# datalogger_v1.net
KiCad netlist of a schematic drawn in EAGLE
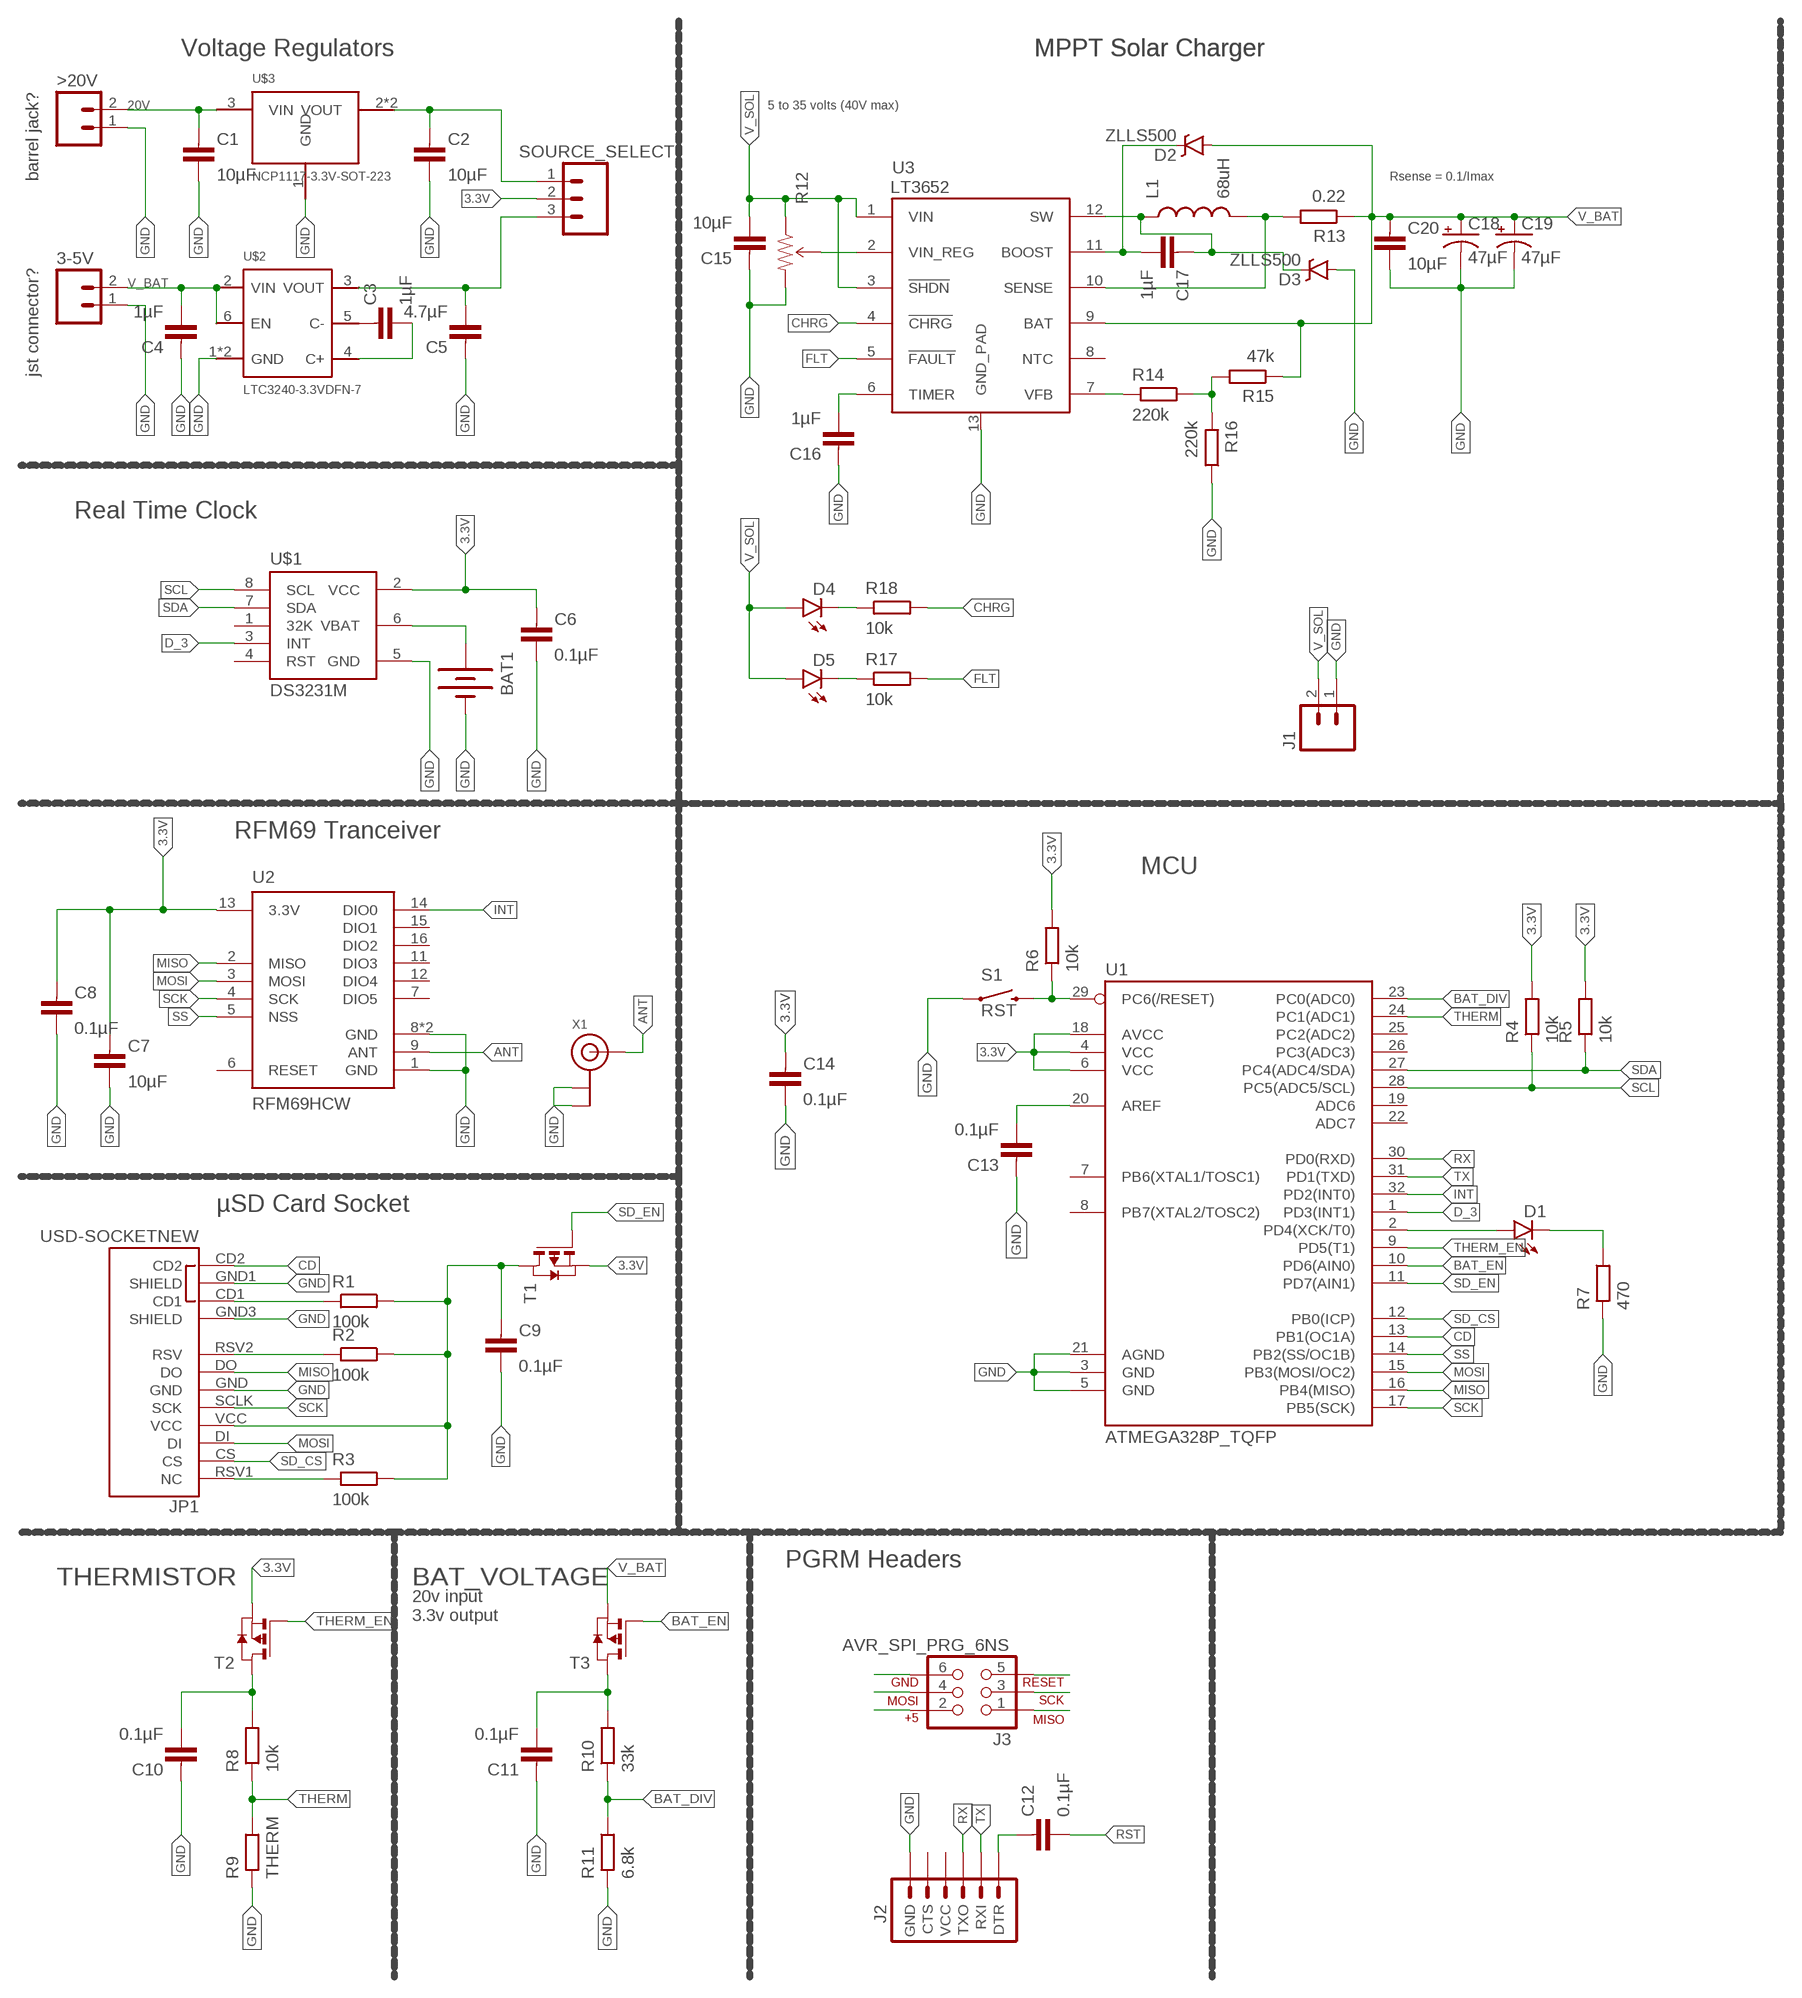
[diagram p0: schematic, sheet 1]

(export (version "E")
  (design (tool "Eeschema 10.0.6"))
  (components
    (comp (ref "3-5V")
      (value "M02LOCK")
      (footprint "eagle-import:1X02_LOCK")
      (libsource (lib "eagle-import") (part "M02LOCK"))
    )
    (comp (ref ">20V")
      (value "M02LOCK")
      (footprint "eagle-import:1X02_LOCK")
      (libsource (lib "eagle-import") (part "M02LOCK"))
    )
    (comp (ref "BAT1")
      (value "BATTERY12MM")
      (footprint "eagle-import:BATTCON_12MM")
      (libsource (lib "eagle-import") (part "BATTERY12MM"))
    )
    (comp (ref "C1")
      (value "10µF")
      (footprint "eagle-import:C0805-N")
      (libsource (lib "eagle-import") (part "CAPACITOR0805-N"))
    )
    (comp (ref "C2")
      (value "10µF")
      (footprint "eagle-import:C0805-N")
      (libsource (lib "eagle-import") (part "CAPACITOR0805-N"))
    )
    (comp (ref "C3")
      (value "1µF")
      (footprint "eagle-import:C0603-N")
      (libsource (lib "eagle-import") (part "CAPACITOR0603-N"))
    )
    (comp (ref "C4")
      (value "1µF")
      (footprint "eagle-import:C0603-N")
      (libsource (lib "eagle-import") (part "CAPACITOR0603-N"))
    )
    (comp (ref "C5")
      (value "4.7µF")
      (footprint "eagle-import:C0603-N")
      (libsource (lib "eagle-import") (part "CAPACITOR0603-N"))
    )
    (comp (ref "C6")
      (value "0.1µF")
      (footprint "eagle-import:C0603-N")
      (libsource (lib "eagle-import") (part "CAPACITOR0603-N"))
    )
    (comp (ref "C7")
      (value "10µF")
      (footprint "eagle-import:C0805-N")
      (libsource (lib "eagle-import") (part "CAPACITOR0805-N"))
    )
    (comp (ref "C8")
      (value "0.1µF")
      (footprint "eagle-import:C0603-N")
      (libsource (lib "eagle-import") (part "CAPACITOR0603-N"))
    )
    (comp (ref "C9")
      (value "0.1µF")
      (footprint "eagle-import:C0603-N")
      (libsource (lib "eagle-import") (part "CAPACITOR0603-N"))
    )
    (comp (ref "C10")
      (value "0.1µF")
      (footprint "eagle-import:C0603-N")
      (libsource (lib "eagle-import") (part "CAPACITOR0603-N"))
    )
    (comp (ref "C11")
      (value "0.1µF")
      (footprint "eagle-import:C0603-N")
      (libsource (lib "eagle-import") (part "CAPACITOR0603-N"))
    )
    (comp (ref "C12")
      (value "0.1µF")
      (footprint "eagle-import:C0603-N")
      (libsource (lib "eagle-import") (part "CAPACITOR0603-N"))
    )
    (comp (ref "C13")
      (value "0.1µF")
      (footprint "eagle-import:C0603-N")
      (libsource (lib "eagle-import") (part "CAPACITOR0603-N"))
    )
    (comp (ref "C14")
      (value "0.1µF")
      (footprint "eagle-import:C0603-N")
      (libsource (lib "eagle-import") (part "CAPACITOR0603-N"))
    )
    (comp (ref "C15")
      (value "10µF")
      (footprint "eagle-import:C0805-N")
      (libsource (lib "eagle-import") (part "CAPACITOR0805-N"))
    )
    (comp (ref "C16")
      (value "1µF")
      (footprint "eagle-import:C0603-N")
      (libsource (lib "eagle-import") (part "CAPACITOR0603-N"))
    )
    (comp (ref "C17")
      (value "1µF")
      (footprint "eagle-import:C0603-N")
      (libsource (lib "eagle-import") (part "CAPACITOR0603-N"))
    )
    (comp (ref "C18")
      (value "47µF")
      (footprint "eagle-import:EN_J2")
      (libsource (lib "eagle-import") (part "CAP_POLEN_J2"))
    )
    (comp (ref "C19")
      (value "47µF")
      (footprint "eagle-import:EN_J2")
      (libsource (lib "eagle-import") (part "CAP_POLEN_J2"))
    )
    (comp (ref "C20")
      (value "10µF")
      (footprint "eagle-import:C0805-N")
      (libsource (lib "eagle-import") (part "CAPACITOR0805-N"))
    )
    (comp (ref "D1")
      (value "LED0603")
      (footprint "eagle-import:LED-0603")
      (libsource (lib "eagle-import") (part "LED0603"))
    )
    (comp (ref "D2")
      (value "ZLLS500")
      (footprint "eagle-import:SOT23-3")
      (libsource (lib "eagle-import") (part "ZLLS500ZLLS500"))
    )
    (comp (ref "D3")
      (value "ZLLS500")
      (footprint "eagle-import:SOT23-3")
      (libsource (lib "eagle-import") (part "ZLLS500ZLLS500"))
    )
    (comp (ref "D4")
      (value "LED0603")
      (footprint "eagle-import:LED-0603")
      (libsource (lib "eagle-import") (part "LED0603"))
    )
    (comp (ref "D5")
      (value "LED0603")
      (footprint "eagle-import:LED-0603")
      (libsource (lib "eagle-import") (part "LED0603"))
    )
    (comp (ref "J1")
      (value "M02LOCK")
      (footprint "eagle-import:1X02_LOCK")
      (libsource (lib "eagle-import") (part "M02LOCK"))
    )
    (comp (ref "J2")
      (value "ARDUINO_SERIAL_PROGRAMLOCK")
      (footprint "eagle-import:1X06_LOCK")
      (libsource (lib "eagle-import") (part "ARDUINO_SERIAL_PROGRAMLOCK"))
    )
    (comp (ref "J3")
      (value "AVR_SPI_PRG_6NS")
      (footprint "eagle-import:2X3-NS")
      (libsource (lib "eagle-import") (part "AVR_SPI_PRG_6NS"))
    )
    (comp (ref "JP1")
      (value "USD-SOCKETNEW")
      (footprint "eagle-import:MICRO-SD-SOCKET-PP")
      (libsource (lib "eagle-import") (part "USD-SOCKETNEW"))
    )
    (comp (ref "L1")
      (value "68uH")
      (footprint "eagle-import:CR75")
      (libsource (lib "eagle-import") (part "INDUCTOR68UH-1A"))
    )
    (comp (ref "R1")
      (value "100k")
      (footprint "eagle-import:R0603-N")
      (libsource (lib "eagle-import") (part "RESISTOR0603-N"))
    )
    (comp (ref "R2")
      (value "100k")
      (footprint "eagle-import:R0603-N")
      (libsource (lib "eagle-import") (part "RESISTOR0603-N"))
    )
    (comp (ref "R3")
      (value "100k")
      (footprint "eagle-import:R0603-N")
      (libsource (lib "eagle-import") (part "RESISTOR0603-N"))
    )
    (comp (ref "R4")
      (value "10k")
      (footprint "eagle-import:R0603-N")
      (libsource (lib "eagle-import") (part "RESISTOR0603-N"))
    )
    (comp (ref "R5")
      (value "10k")
      (footprint "eagle-import:R0603-N")
      (libsource (lib "eagle-import") (part "RESISTOR0603-N"))
    )
    (comp (ref "R6")
      (value "10k")
      (footprint "eagle-import:R0603-N")
      (libsource (lib "eagle-import") (part "RESISTOR0603-N"))
    )
    (comp (ref "R7")
      (value "470")
      (footprint "eagle-import:R0603-N")
      (libsource (lib "eagle-import") (part "RESISTOR0603-N"))
    )
    (comp (ref "R8")
      (value "10k")
      (footprint "eagle-import:R0603-N")
      (libsource (lib "eagle-import") (part "RESISTOR0603-N"))
    )
    (comp (ref "R9")
      (value "THERM")
      (footprint "eagle-import:R0603-N")
      (libsource (lib "eagle-import") (part "RESISTOR0603-N"))
    )
    (comp (ref "R10")
      (value "33k")
      (footprint "eagle-import:R0603-N")
      (libsource (lib "eagle-import") (part "RESISTOR0603-N"))
    )
    (comp (ref "R11")
      (value "6.8k")
      (footprint "eagle-import:R0603-N")
      (libsource (lib "eagle-import") (part "RESISTOR0603-N"))
    )
    (comp (ref "R12")
      (value "TRIMPOT")
      (footprint "eagle-import:TRIMPOT-5MM-V2")
      (libsource (lib "eagle-import") (part "TRIMPOT"))
    )
    (comp (ref "R13")
      (value "0.22")
      (footprint "eagle-import:R0603-N")
      (libsource (lib "eagle-import") (part "RESISTOR0603-N"))
    )
    (comp (ref "R14")
      (value "220k")
      (footprint "eagle-import:R0603-N")
      (libsource (lib "eagle-import") (part "RESISTOR0603-N"))
    )
    (comp (ref "R15")
      (value "47k")
      (footprint "eagle-import:R0603-N")
      (libsource (lib "eagle-import") (part "RESISTOR0603-N"))
    )
    (comp (ref "R16")
      (value "220k")
      (footprint "eagle-import:R0603-N")
      (libsource (lib "eagle-import") (part "RESISTOR0603-N"))
    )
    (comp (ref "R17")
      (value "10k")
      (footprint "eagle-import:R0603-N")
      (libsource (lib "eagle-import") (part "RESISTOR0603-N"))
    )
    (comp (ref "R18")
      (value "10k")
      (footprint "eagle-import:R0603-N")
      (libsource (lib "eagle-import") (part "RESISTOR0603-N"))
    )
    (comp (ref "S1")
      (value "RST")
      (footprint "eagle-import:TACTILE_SWITCH_SMD_4.6X2.8MM")
      (libsource (lib "eagle-import") (part "SWITCH-MOMENTARY-2SMD-4.6X2.8MM"))
    )
    (comp (ref "SOURCE_SELECT")
      (value "M03LOCK")
      (footprint "eagle-import:1X03_LOCK")
      (libsource (lib "eagle-import") (part "M03LOCK"))
    )
    (comp (ref "T1")
      (value "PMOSSOT23")
      (footprint "eagle-import:SOT-23")
      (libsource (lib "eagle-import") (part "PMOSSOT23"))
    )
    (comp (ref "T2")
      (value "PMOSSOT23")
      (footprint "eagle-import:SOT-23")
      (libsource (lib "eagle-import") (part "PMOSSOT23"))
    )
    (comp (ref "T3")
      (value "PMOSSOT23")
      (footprint "eagle-import:SOT-23")
      (libsource (lib "eagle-import") (part "PMOSSOT23"))
    )
    (comp (ref "U$1")
      (value "DS3231M")
      (footprint "eagle-import:SO08")
      (libsource (lib "eagle-import") (part "DS3231M"))
    )
    (comp (ref "U$2")
      (value "LTC3240-3.3VDFN-7")
      (footprint "eagle-import:DFN200X200X80-7N")
      (libsource (lib "eagle-import") (part "LTC3240-3.3VDFN-7"))
    )
    (comp (ref "U$3")
      (value "NCP1117-3.3V-SOT-223")
      (footprint "eagle-import:SOT223")
      (libsource (lib "eagle-import") (part "NCP1117-3.3V-SOT-223"))
    )
    (comp (ref "U1")
      (value "ATMEGA328P_TQFP")
      (footprint "eagle-import:TQFP32-08")
      (libsource (lib "eagle-import") (part "ATMEGA328P_TQFP"))
    )
    (comp (ref "U2")
      (value "RFM69HCW")
      (footprint "eagle-import:RFM69HCW-XXXS2")
      (libsource (lib "eagle-import") (part "RFM69HCW"))
    )
    (comp (ref "U3")
      (value "LT3652")
      (footprint "eagle-import:MSOP-12_GND")
      (libsource (lib "eagle-import") (part "LT3652"))
    )
    (comp (ref "X1")
      (value "ADAFRUIT_ANTENNA_U.FL")
      (footprint "eagle-import:ADAFRUIT_U.FL")
      (libsource (lib "eagle-import") (part "ADAFRUIT_ANTENNA_U.FL"))
    )
  )
  (nets
    (net (code "1") (name "/20V") (class "Default")
      (node (ref ">20V") (pin "2") (pinfunction "2_2") (pintype "passive"))
      (node (ref "C1") (pin "1") (pinfunction "1_1") (pintype "passive"))
      (node (ref "U$3") (pin "3") (pinfunction "VIN_3") (pintype "bidirectional"))
    )
    (net (code "2") (name "3.3V") (class "Default")
      (node (ref "C14") (pin "1") (pinfunction "1_1") (pintype "passive"))
      (node (ref "C6") (pin "1") (pinfunction "1_1") (pintype "passive"))
      (node (ref "C7") (pin "1") (pinfunction "1_1") (pintype "passive"))
      (node (ref "C8") (pin "1") (pinfunction "1_1") (pintype "passive"))
      (node (ref "J3") (pin "2") (pinfunction "2_2") (pintype "passive"))
      (node (ref "R4") (pin "2") (pinfunction "P$2_2") (pintype "passive"))
      (node (ref "R5") (pin "2") (pinfunction "P$2_2") (pintype "passive"))
      (node (ref "R6") (pin "2") (pinfunction "P$2_2") (pintype "passive"))
      (node (ref "SOURCE_SELECT") (pin "2") (pinfunction "2_2") (pintype "passive"))
      (node (ref "T1") (pin "2") (pinfunction "S_2") (pintype "passive"))
      (node (ref "T2") (pin "2") (pinfunction "S_2") (pintype "passive"))
      (node (ref "U$1") (pin "2") (pinfunction "VCC_2") (pintype "power_in"))
      (node (ref "U1") (pin "18") (pinfunction "AVCC_18") (pintype "bidirectional"))
      (node (ref "U1") (pin "4") (pinfunction "VCC_4") (pintype "bidirectional"))
      (node (ref "U1") (pin "6") (pinfunction "VCC_6") (pintype "bidirectional"))
      (node (ref "U2") (pin "13") (pinfunction "3.3V_13") (pintype "power_in"))
    )
    (net (code "3") (name "ANT") (class "Default")
      (node (ref "U2") (pin "9") (pinfunction "ANT_9") (pintype "passive"))
      (node (ref "X1") (pin "3") (pinfunction "SIGNAL_3") (pintype "passive"))
    )
    (net (code "4") (name "BAT_DIV") (class "Default")
      (node (ref "R10") (pin "1") (pinfunction "P$1_1") (pintype "passive"))
      (node (ref "R11") (pin "2") (pinfunction "P$2_2") (pintype "passive"))
      (node (ref "U1") (pin "23") (pinfunction "PC0(ADC0)_23") (pintype "bidirectional"))
    )
    (net (code "5") (name "BAT_EN") (class "Default")
      (node (ref "T3") (pin "3") (pinfunction "G_3") (pintype "passive"))
      (node (ref "U1") (pin "10") (pinfunction "PD6(AIN0)_10") (pintype "bidirectional"))
    )
    (net (code "6") (name "CD") (class "Default")
      (node (ref "JP1") (pin "CD2") (pinfunction "CD2_CD2") (pintype "bidirectional"))
      (node (ref "U1") (pin "13") (pinfunction "PB1(OC1A)_13") (pintype "bidirectional"))
    )
    (net (code "7") (name "CHRG") (class "Default")
      (node (ref "R18") (pin "2") (pinfunction "P$2_2") (pintype "passive"))
      (node (ref "U3") (pin "4") (pinfunction "~{CHRG}_4") (pintype "bidirectional"))
    )
    (net (code "8") (name "D_3") (class "Default")
      (node (ref "U$1") (pin "3") (pinfunction "INT_3") (pintype "bidirectional"))
      (node (ref "U1") (pin "1") (pinfunction "PD3(INT1)_1") (pintype "bidirectional"))
    )
    (net (code "9") (name "FLT") (class "Default")
      (node (ref "R17") (pin "2") (pinfunction "P$2_2") (pintype "passive"))
      (node (ref "U3") (pin "5") (pinfunction "~{FAULT}_5") (pintype "bidirectional"))
    )
    (net (code "10") (name "GND") (class "Default")
      (node (ref "3-5V") (pin "1") (pinfunction "1_1") (pintype "passive"))
      (node (ref ">20V") (pin "1") (pinfunction "1_1") (pintype "passive"))
      (node (ref "BAT1") (pin "GND") (pinfunction "-_GND") (pintype "power_in"))
      (node (ref "C1") (pin "2") (pinfunction "2_2") (pintype "passive"))
      (node (ref "C10") (pin "1") (pinfunction "1_1") (pintype "passive"))
      (node (ref "C11") (pin "1") (pinfunction "1_1") (pintype "passive"))
      (node (ref "C13") (pin "1") (pinfunction "1_1") (pintype "passive"))
      (node (ref "C14") (pin "2") (pinfunction "2_2") (pintype "passive"))
      (node (ref "C15") (pin "1") (pinfunction "1_1") (pintype "passive"))
      (node (ref "C16") (pin "1") (pinfunction "1_1") (pintype "passive"))
      (node (ref "C18") (pin "-") (pinfunction "-_-") (pintype "passive"))
      (node (ref "C19") (pin "-") (pinfunction "-_-") (pintype "passive"))
      (node (ref "C2") (pin "2") (pinfunction "2_2") (pintype "passive"))
      (node (ref "C20") (pin "2") (pinfunction "2_2") (pintype "passive"))
      (node (ref "C4") (pin "1") (pinfunction "1_1") (pintype "passive"))
      (node (ref "C5") (pin "1") (pinfunction "1_1") (pintype "passive"))
      (node (ref "C6") (pin "2") (pinfunction "2_2") (pintype "passive"))
      (node (ref "C7") (pin "2") (pinfunction "2_2") (pintype "passive"))
      (node (ref "C8") (pin "2") (pinfunction "2_2") (pintype "passive"))
      (node (ref "C9") (pin "2") (pinfunction "2_2") (pintype "passive"))
      (node (ref "D3") (pin "1") (pinfunction "A_1") (pintype "passive"))
      (node (ref "J1") (pin "1") (pinfunction "1_1") (pintype "passive"))
      (node (ref "J2") (pin "6") (pinfunction "GND_6") (pintype "passive"))
      (node (ref "J3") (pin "6") (pinfunction "6_6") (pintype "passive"))
      (node (ref "JP1") (pin "GND") (pinfunction "GND_GND") (pintype "bidirectional"))
      (node (ref "JP1") (pin "GND1") (pinfunction "SHIELD_GND1") (pintype "bidirectional"))
      (node (ref "JP1") (pin "GND3") (pinfunction "SHIELD_GND3") (pintype "bidirectional"))
      (node (ref "R11") (pin "1") (pinfunction "P$1_1") (pintype "passive"))
      (node (ref "R12") (pin "C") (pinfunction "CW_C") (pintype "passive"))
      (node (ref "R16") (pin "2") (pinfunction "P$2_2") (pintype "passive"))
      (node (ref "R7") (pin "1") (pinfunction "P$1_1") (pintype "passive"))
      (node (ref "R9") (pin "1") (pinfunction "P$1_1") (pintype "passive"))
      (node (ref "S1") (pin "1") (pinfunction "1_1") (pintype "passive"))
      (node (ref "S1") (pin "2") (pinfunction "1_2") (pintype "passive"))
      (node (ref "U$1") (pin "5") (pinfunction "GND_5") (pintype "power_in"))
      (node (ref "U$2") (pin "1") (pinfunction "GND_1") (pintype "bidirectional"))
      (node (ref "U$2") (pin "7") (pinfunction "GND_7") (pintype "bidirectional"))
      (node (ref "U$3") (pin "1") (pinfunction "GND_1") (pintype "bidirectional"))
      (node (ref "U1") (pin "21") (pinfunction "AGND_21") (pintype "bidirectional"))
      (node (ref "U1") (pin "3") (pinfunction "GND_3") (pintype "bidirectional"))
      (node (ref "U1") (pin "5") (pinfunction "GND_5") (pintype "bidirectional"))
      (node (ref "U2") (pin "1") (pinfunction "GND_1") (pintype "power_in"))
      (node (ref "U2") (pin "10") (pinfunction "GND_10") (pintype "power_in"))
      (node (ref "U2") (pin "8") (pinfunction "GND_8") (pintype "power_in"))
      (node (ref "U3") (pin "13") (pinfunction "GND_PAD_13") (pintype "bidirectional"))
      (node (ref "X1") (pin "1") (pinfunction "GND_1") (pintype "passive"))
      (node (ref "X1") (pin "2") (pinfunction "GND_2") (pintype "passive"))
    )
    (net (code "11") (name "INT") (class "Default")
      (node (ref "U1") (pin "32") (pinfunction "PD2(INT0)_32") (pintype "bidirectional"))
      (node (ref "U2") (pin "14") (pinfunction "DIO0_14") (pintype "bidirectional"))
    )
    (net (code "12") (name "MISO") (class "Default")
      (node (ref "J3") (pin "1") (pinfunction "1_1") (pintype "passive"))
      (node (ref "JP1") (pin "DO") (pinfunction "DO_DO") (pintype "bidirectional"))
      (node (ref "U1") (pin "16") (pinfunction "PB4(MISO)_16") (pintype "bidirectional"))
      (node (ref "U2") (pin "2") (pinfunction "MISO_2") (pintype "bidirectional"))
    )
    (net (code "13") (name "MOSI") (class "Default")
      (node (ref "J3") (pin "4") (pinfunction "4_4") (pintype "passive"))
      (node (ref "JP1") (pin "DI") (pinfunction "DI_DI") (pintype "bidirectional"))
      (node (ref "U1") (pin "15") (pinfunction "PB3(MOSI/OC2)_15") (pintype "bidirectional"))
      (node (ref "U2") (pin "3") (pinfunction "MOSI_3") (pintype "input"))
    )
    (net (code "14") (name "Net-(BAT1-+)") (class "Default")
      (node (ref "BAT1") (pin "PWR@1") (pinfunction "+_PWR@1") (pintype "power_in"))
      (node (ref "U$1") (pin "6") (pinfunction "VBAT_6") (pintype "power_in"))
    )
    (net (code "15") (name "Net-(C2-Pad1)") (class "Default")
      (node (ref "C2") (pin "1") (pinfunction "1_1") (pintype "passive"))
      (node (ref "SOURCE_SELECT") (pin "1") (pinfunction "1_1") (pintype "passive"))
      (node (ref "U$3") (pin "2") (pinfunction "VOUT_2") (pintype "bidirectional"))
      (node (ref "U$3") (pin "4") (pinfunction "VOUT_4") (pintype "bidirectional"))
    )
    (net (code "16") (name "Net-(D2-C)") (class "Default")
      (node (ref "C17") (pin "2") (pinfunction "2_2") (pintype "passive"))
      (node (ref "D2") (pin "3") (pinfunction "C_3") (pintype "passive"))
      (node (ref "U3") (pin "11") (pinfunction "BOOST_11") (pintype "bidirectional"))
    )
    (net (code "17") (name "Net-(D3-C)") (class "Default")
      (node (ref "C17") (pin "1") (pinfunction "1_1") (pintype "passive"))
      (node (ref "D3") (pin "3") (pinfunction "C_3") (pintype "passive"))
      (node (ref "L1") (pin "P$1") (pinfunction "1_P$1") (pintype "passive"))
      (node (ref "U3") (pin "12") (pinfunction "SW_12") (pintype "bidirectional"))
    )
    (net (code "18") (name "Net-(J2-DTR)") (class "Default")
      (node (ref "C12") (pin "1") (pinfunction "1_1") (pintype "passive"))
      (node (ref "J2") (pin "1") (pinfunction "DTR_1") (pintype "passive"))
    )
    (net (code "19") (name "Net-(JP1-NC)") (class "Default")
      (node (ref "JP1") (pin "RSV1") (pinfunction "NC_RSV1") (pintype "bidirectional"))
      (node (ref "R3") (pin "1") (pinfunction "P$1_1") (pintype "passive"))
    )
    (net (code "20") (name "Net-(JP1-RSV)") (class "Default")
      (node (ref "JP1") (pin "RSV2") (pinfunction "RSV_RSV2") (pintype "bidirectional"))
      (node (ref "R2") (pin "1") (pinfunction "P$1_1") (pintype "passive"))
    )
    (net (code "21") (name "Net-(L1-2)") (class "Default")
      (node (ref "L1") (pin "P$2") (pinfunction "2_P$2") (pintype "passive"))
      (node (ref "R13") (pin "2") (pinfunction "P$2_2") (pintype "passive"))
      (node (ref "U3") (pin "10") (pinfunction "SENSE_10") (pintype "bidirectional"))
    )
    (net (code "22") (name "Net-(R1-P$1)") (class "Default")
      (node (ref "JP1") (pin "CD1") (pinfunction "CD1_CD1") (pintype "bidirectional"))
      (node (ref "R1") (pin "1") (pinfunction "P$1_1") (pintype "passive"))
    )
    (net (code "23") (name "Net-(R1-P$2)") (class "Default")
      (node (ref "C9") (pin "1") (pinfunction "1_1") (pintype "passive"))
      (node (ref "JP1") (pin "VCC") (pinfunction "VCC_VCC") (pintype "bidirectional"))
      (node (ref "R1") (pin "2") (pinfunction "P$2_2") (pintype "passive"))
      (node (ref "R2") (pin "2") (pinfunction "P$2_2") (pintype "passive"))
      (node (ref "R3") (pin "2") (pinfunction "P$2_2") (pintype "passive"))
      (node (ref "T1") (pin "1") (pinfunction "D_1") (pintype "passive"))
    )
    (net (code "24") (name "Net-(R7-P$2)") (class "Default")
      (node (ref "D1") (pin "C") (pinfunction "C_C") (pintype "passive"))
      (node (ref "R7") (pin "2") (pinfunction "P$2_2") (pintype "passive"))
    )
    (net (code "25") (name "Net-(R8-P$2)") (class "Default")
      (node (ref "C10") (pin "2") (pinfunction "2_2") (pintype "passive"))
      (node (ref "R8") (pin "2") (pinfunction "P$2_2") (pintype "passive"))
      (node (ref "T2") (pin "1") (pinfunction "D_1") (pintype "passive"))
    )
    (net (code "26") (name "Net-(R10-P$2)") (class "Default")
      (node (ref "C11") (pin "2") (pinfunction "2_2") (pintype "passive"))
      (node (ref "R10") (pin "2") (pinfunction "P$2_2") (pintype "passive"))
      (node (ref "T3") (pin "1") (pinfunction "D_1") (pintype "passive"))
    )
    (net (code "27") (name "Net-(R12-WIPER)") (class "Default")
      (node (ref "R12") (pin "B") (pinfunction "WIPER_B") (pintype "passive"))
      (node (ref "U3") (pin "2") (pinfunction "VIN_REG_2") (pintype "bidirectional"))
    )
    (net (code "28") (name "Net-(R14-P$1)") (class "Default")
      (node (ref "R14") (pin "1") (pinfunction "P$1_1") (pintype "passive"))
      (node (ref "U3") (pin "7") (pinfunction "VFB_7") (pintype "bidirectional"))
    )
    (net (code "29") (name "Net-(R14-P$2)") (class "Default")
      (node (ref "R14") (pin "2") (pinfunction "P$2_2") (pintype "passive"))
      (node (ref "R15") (pin "2") (pinfunction "P$2_2") (pintype "passive"))
      (node (ref "R16") (pin "1") (pinfunction "P$1_1") (pintype "passive"))
    )
    (net (code "30") (name "Net-(R17-P$1)") (class "Default")
      (node (ref "D5") (pin "C") (pinfunction "C_C") (pintype "passive"))
      (node (ref "R17") (pin "1") (pinfunction "P$1_1") (pintype "passive"))
    )
    (net (code "31") (name "Net-(R18-P$1)") (class "Default")
      (node (ref "D4") (pin "C") (pinfunction "C_C") (pintype "passive"))
      (node (ref "R18") (pin "1") (pinfunction "P$1_1") (pintype "passive"))
    )
    (net (code "32") (name "Net-(U$2-C+)") (class "Default")
      (node (ref "C3") (pin "2") (pinfunction "2_2") (pintype "passive"))
      (node (ref "U$2") (pin "4") (pinfunction "C+_4") (pintype "bidirectional"))
    )
    (net (code "33") (name "Net-(U$2-C-)") (class "Default")
      (node (ref "C3") (pin "1") (pinfunction "1_1") (pintype "passive"))
      (node (ref "U$2") (pin "5") (pinfunction "C-_5") (pintype "bidirectional"))
    )
    (net (code "34") (name "Net-(U$2-VOUT)") (class "Default")
      (node (ref "C5") (pin "2") (pinfunction "2_2") (pintype "passive"))
      (node (ref "SOURCE_SELECT") (pin "3") (pinfunction "3_3") (pintype "passive"))
      (node (ref "U$2") (pin "3") (pinfunction "VOUT_3") (pintype "bidirectional"))
    )
    (net (code "35") (name "Net-(U1-AREF)") (class "Default")
      (node (ref "C13") (pin "2") (pinfunction "2_2") (pintype "passive"))
      (node (ref "U1") (pin "20") (pinfunction "AREF_20") (pintype "bidirectional"))
    )
    (net (code "36") (name "Net-(U1-PD4(XCK{slash}T0))") (class "Default")
      (node (ref "D1") (pin "A") (pinfunction "A_A") (pintype "passive"))
      (node (ref "U1") (pin "2") (pinfunction "PD4(XCK/T0)_2") (pintype "bidirectional"))
    )
    (net (code "37") (name "Net-(U3-TIMER)") (class "Default")
      (node (ref "C16") (pin "2") (pinfunction "2_2") (pintype "passive"))
      (node (ref "U3") (pin "6") (pinfunction "TIMER_6") (pintype "bidirectional"))
    )
    (net (code "38") (name "RST") (class "Default")
      (node (ref "C12") (pin "2") (pinfunction "2_2") (pintype "passive"))
      (node (ref "J3") (pin "5") (pinfunction "5_5") (pintype "passive"))
      (node (ref "R6") (pin "1") (pinfunction "P$1_1") (pintype "passive"))
      (node (ref "S1") (pin "3") (pinfunction "2_3") (pintype "passive"))
      (node (ref "S1") (pin "4") (pinfunction "2_4") (pintype "passive"))
      (node (ref "U1") (pin "29") (pinfunction "PC6(/RESET)_29") (pintype "bidirectional"))
    )
    (net (code "39") (name "RX") (class "Default")
      (node (ref "J2") (pin "3") (pinfunction "TXO_3") (pintype "passive"))
      (node (ref "U1") (pin "30") (pinfunction "PD0(RXD)_30") (pintype "bidirectional"))
    )
    (net (code "40") (name "SCK") (class "Default")
      (node (ref "J3") (pin "3") (pinfunction "3_3") (pintype "passive"))
      (node (ref "JP1") (pin "SCLK") (pinfunction "SCK_SCLK") (pintype "bidirectional"))
      (node (ref "U1") (pin "17") (pinfunction "PB5(SCK)_17") (pintype "bidirectional"))
      (node (ref "U2") (pin "4") (pinfunction "SCK_4") (pintype "input"))
    )
    (net (code "41") (name "SCL") (class "Default")
      (node (ref "R4") (pin "1") (pinfunction "P$1_1") (pintype "passive"))
      (node (ref "U$1") (pin "8") (pinfunction "SCL_8") (pintype "bidirectional"))
      (node (ref "U1") (pin "28") (pinfunction "PC5(ADC5/SCL)_28") (pintype "bidirectional"))
    )
    (net (code "42") (name "SDA") (class "Default")
      (node (ref "R5") (pin "1") (pinfunction "P$1_1") (pintype "passive"))
      (node (ref "U$1") (pin "7") (pinfunction "SDA_7") (pintype "bidirectional"))
      (node (ref "U1") (pin "27") (pinfunction "PC4(ADC4/SDA)_27") (pintype "bidirectional"))
    )
    (net (code "43") (name "SD_CS") (class "Default")
      (node (ref "JP1") (pin "CS") (pinfunction "CS_CS") (pintype "bidirectional"))
      (node (ref "U1") (pin "12") (pinfunction "PB0(ICP)_12") (pintype "bidirectional"))
    )
    (net (code "44") (name "SD_EN") (class "Default")
      (node (ref "T1") (pin "3") (pinfunction "G_3") (pintype "passive"))
      (node (ref "U1") (pin "11") (pinfunction "PD7(AIN1)_11") (pintype "bidirectional"))
    )
    (net (code "45") (name "SS") (class "Default")
      (node (ref "U1") (pin "14") (pinfunction "PB2(SS/OC1B)_14") (pintype "bidirectional"))
      (node (ref "U2") (pin "5") (pinfunction "NSS_5") (pintype "input"))
    )
    (net (code "46") (name "THERM") (class "Default")
      (node (ref "R8") (pin "1") (pinfunction "P$1_1") (pintype "passive"))
      (node (ref "R9") (pin "2") (pinfunction "P$2_2") (pintype "passive"))
      (node (ref "U1") (pin "24") (pinfunction "PC1(ADC1)_24") (pintype "bidirectional"))
    )
    (net (code "47") (name "THERM_EN") (class "Default")
      (node (ref "T2") (pin "3") (pinfunction "G_3") (pintype "passive"))
      (node (ref "U1") (pin "9") (pinfunction "PD5(T1)_9") (pintype "bidirectional"))
    )
    (net (code "48") (name "TX") (class "Default")
      (node (ref "J2") (pin "2") (pinfunction "RXI_2") (pintype "passive"))
      (node (ref "U1") (pin "31") (pinfunction "PD1(TXD)_31") (pintype "bidirectional"))
    )
    (net (code "49") (name "V_BAT") (class "Default")
      (node (ref "3-5V") (pin "2") (pinfunction "2_2") (pintype "passive"))
      (node (ref "C18") (pin "+") (pinfunction "+_+") (pintype "passive"))
      (node (ref "C19") (pin "+") (pinfunction "+_+") (pintype "passive"))
      (node (ref "C20") (pin "1") (pinfunction "1_1") (pintype "passive"))
      (node (ref "C4") (pin "2") (pinfunction "2_2") (pintype "passive"))
      (node (ref "D2") (pin "1") (pinfunction "A_1") (pintype "passive"))
      (node (ref "R13") (pin "1") (pinfunction "P$1_1") (pintype "passive"))
      (node (ref "R15") (pin "1") (pinfunction "P$1_1") (pintype "passive"))
      (node (ref "T3") (pin "2") (pinfunction "S_2") (pintype "passive"))
      (node (ref "U$2") (pin "2") (pinfunction "VIN_2") (pintype "bidirectional"))
      (node (ref "U$2") (pin "6") (pinfunction "EN_6") (pintype "bidirectional"))
      (node (ref "U3") (pin "9") (pinfunction "BAT_9") (pintype "bidirectional"))
    )
    (net (code "50") (name "V_SOL") (class "Default")
      (node (ref "C15") (pin "2") (pinfunction "2_2") (pintype "passive"))
      (node (ref "D4") (pin "A") (pinfunction "A_A") (pintype "passive"))
      (node (ref "D5") (pin "A") (pinfunction "A_A") (pintype "passive"))
      (node (ref "J1") (pin "2") (pinfunction "2_2") (pintype "passive"))
      (node (ref "R12") (pin "A") (pinfunction "CCW_A") (pintype "passive"))
      (node (ref "U3") (pin "1") (pinfunction "VIN_1") (pintype "bidirectional"))
      (node (ref "U3") (pin "3") (pinfunction "~{SHDN}_3") (pintype "bidirectional"))
    )
    (net (code "51") (name "unconnected-(J2-CTS-Pad5)") (class "Default")
      (node (ref "J2") (pin "5") (pinfunction "CTS_5") (pintype "passive"))
    )
    (net (code "52") (name "unconnected-(J2-VCC-Pad4)") (class "Default")
      (node (ref "J2") (pin "4") (pinfunction "VCC_4") (pintype "passive"))
    )
    (net (code "53") (name "unconnected-(U$1-32K-Pad1)") (class "Default")
      (node (ref "U$1") (pin "1") (pinfunction "32K_1") (pintype "bidirectional"))
    )
    (net (code "54") (name "unconnected-(U$1-RST-Pad4)") (class "Default")
      (node (ref "U$1") (pin "4") (pinfunction "RST_4") (pintype "bidirectional"))
    )
    (net (code "55") (name "unconnected-(U1-ADC6-Pad19)") (class "Default")
      (node (ref "U1") (pin "19") (pinfunction "ADC6_19") (pintype "bidirectional"))
    )
    (net (code "56") (name "unconnected-(U1-ADC7-Pad22)") (class "Default")
      (node (ref "U1") (pin "22") (pinfunction "ADC7_22") (pintype "bidirectional"))
    )
    (net (code "57") (name "unconnected-(U1-PB6(XTAL1{slash}TOSC1)-Pad7)") (class "Default")
      (node (ref "U1") (pin "7") (pinfunction "PB6(XTAL1/TOSC1)_7") (pintype "bidirectional"))
    )
    (net (code "58") (name "unconnected-(U1-PB7(XTAL2{slash}TOSC2)-Pad8)") (class "Default")
      (node (ref "U1") (pin "8") (pinfunction "PB7(XTAL2/TOSC2)_8") (pintype "bidirectional"))
    )
    (net (code "59") (name "unconnected-(U1-PC2(ADC2)-Pad25)") (class "Default")
      (node (ref "U1") (pin "25") (pinfunction "PC2(ADC2)_25") (pintype "bidirectional"))
    )
    (net (code "60") (name "unconnected-(U1-PC3(ADC3)-Pad26)") (class "Default")
      (node (ref "U1") (pin "26") (pinfunction "PC3(ADC3)_26") (pintype "bidirectional"))
    )
    (net (code "61") (name "unconnected-(U2-DIO1-Pad15)") (class "Default")
      (node (ref "U2") (pin "15") (pinfunction "DIO1_15") (pintype "bidirectional"))
    )
    (net (code "62") (name "unconnected-(U2-DIO2-Pad16)") (class "Default")
      (node (ref "U2") (pin "16") (pinfunction "DIO2_16") (pintype "bidirectional"))
    )
    (net (code "63") (name "unconnected-(U2-DIO3-Pad11)") (class "Default")
      (node (ref "U2") (pin "11") (pinfunction "DIO3_11") (pintype "bidirectional"))
    )
    (net (code "64") (name "unconnected-(U2-DIO4-Pad12)") (class "Default")
      (node (ref "U2") (pin "12") (pinfunction "DIO4_12") (pintype "bidirectional"))
    )
    (net (code "65") (name "unconnected-(U2-DIO5-Pad7)") (class "Default")
      (node (ref "U2") (pin "7") (pinfunction "DIO5_7") (pintype "bidirectional"))
    )
    (net (code "66") (name "unconnected-(U2-RESET-Pad6)") (class "Default")
      (node (ref "U2") (pin "6") (pinfunction "RESET_6") (pintype "input"))
    )
    (net (code "67") (name "unconnected-(U3-NTC-Pad8)") (class "Default")
      (node (ref "U3") (pin "8") (pinfunction "NTC_8") (pintype "bidirectional"))
    )
  )
)
